# haasoscope_pro_power_board_-_5V.net
KiCad netlist of a schematic drawn in EAGLE
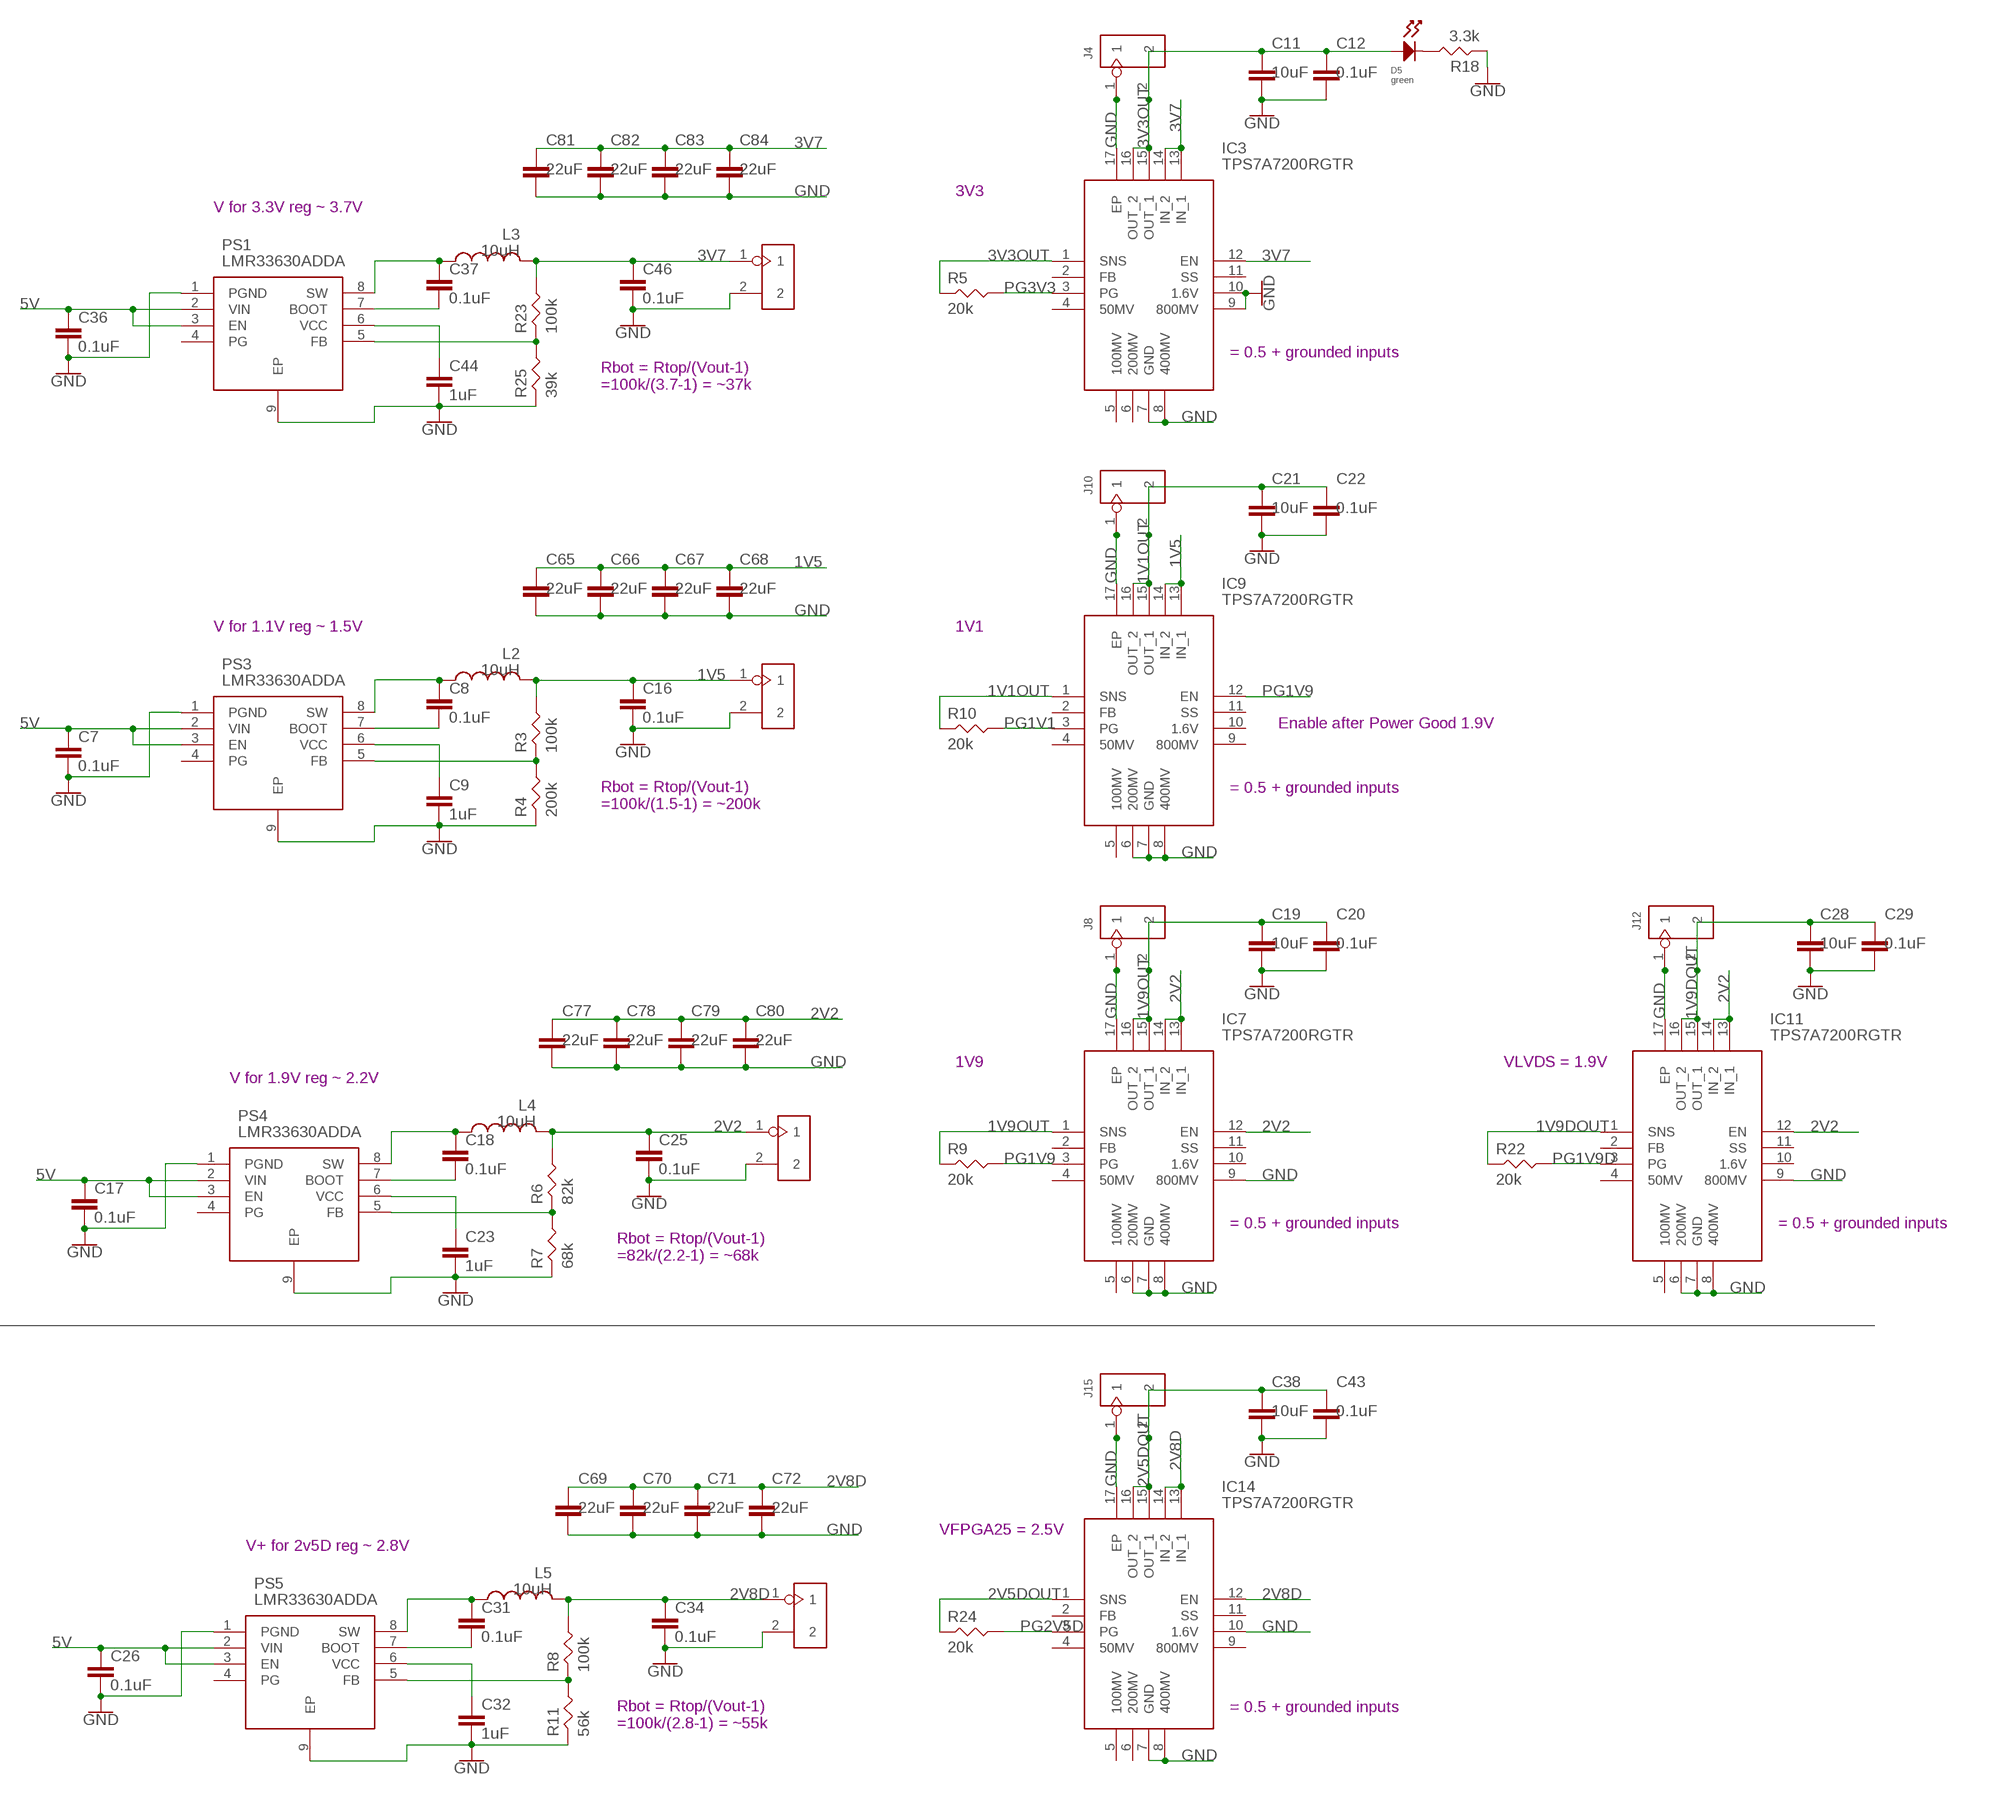
[diagram p0: schematic, sheet 1, part 1 of 2]
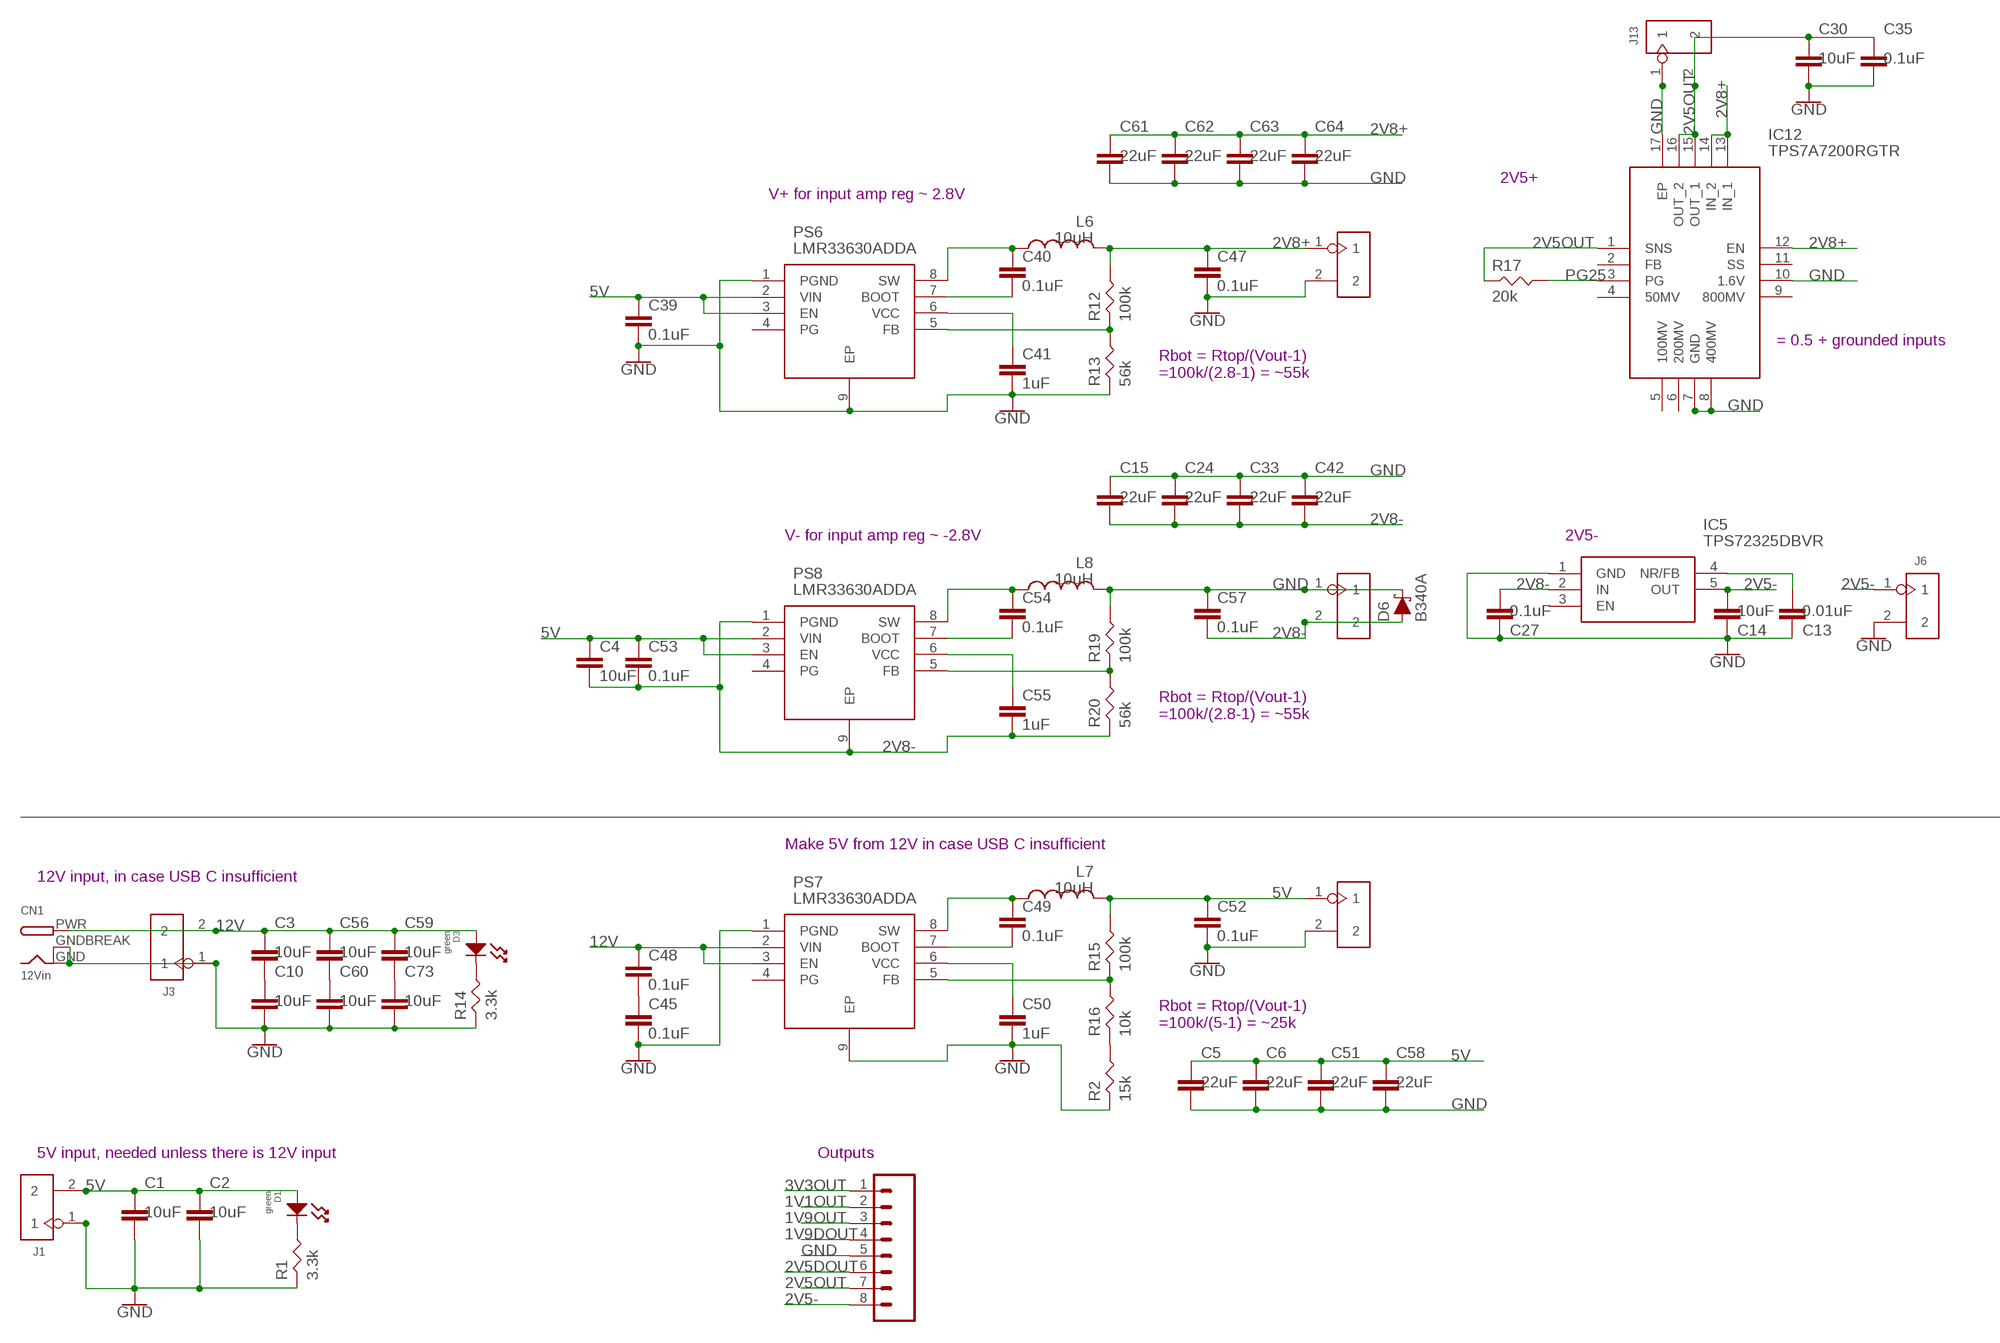
[diagram p1: schematic, sheet 1, part 2 of 2]

(export (version "E")
  (design (tool "Eeschema 10.0.6"))
  (components
    (comp (ref "C1")
      (value "10uF")
      (footprint "eagle-import:RESC0805_N")
      (libsource (lib "eagle-import") (part "CAPACITOR_0805_N"))
    )
    (comp (ref "C2")
      (value "10uF")
      (footprint "eagle-import:RESC0805_N")
      (libsource (lib "eagle-import") (part "CAPACITOR_0805_N"))
    )
    (comp (ref "C3")
      (value "10uF")
      (footprint "eagle-import:RESC0805_N")
      (libsource (lib "eagle-import") (part "CAPACITOR_0805_N"))
    )
    (comp (ref "C4")
      (value "10uF")
      (footprint "eagle-import:RESC0805_N")
      (libsource (lib "eagle-import") (part "CAPACITOR_0805_N"))
    )
    (comp (ref "C5")
      (value "22uF")
      (footprint "eagle-import:RESC0805_N")
      (libsource (lib "eagle-import") (part "CAPACITOR_0805_N"))
    )
    (comp (ref "C6")
      (value "22uF")
      (footprint "eagle-import:RESC0805_N")
      (libsource (lib "eagle-import") (part "CAPACITOR_0805_N"))
    )
    (comp (ref "C7")
      (value "0.1uF")
      (footprint "eagle-import:RESC0402_N")
      (libsource (lib "eagle-import") (part "CAPACITOR_0402_N"))
    )
    (comp (ref "C8")
      (value "0.1uF")
      (footprint "eagle-import:RESC0402_N")
      (libsource (lib "eagle-import") (part "CAPACITOR_0402_N"))
    )
    (comp (ref "C9")
      (value "1uF")
      (footprint "eagle-import:RESC0402_N")
      (libsource (lib "eagle-import") (part "CAPACITOR_0402_N"))
    )
    (comp (ref "C10")
      (value "10uF")
      (footprint "eagle-import:RESC0805_N")
      (libsource (lib "eagle-import") (part "CAPACITOR_0805_N"))
    )
    (comp (ref "C11")
      (value "10uF")
      (footprint "eagle-import:RESC0805_N")
      (libsource (lib "eagle-import") (part "CAPACITOR_0805_N"))
    )
    (comp (ref "C12")
      (value "0.1uF")
      (footprint "eagle-import:RESC0402_N")
      (libsource (lib "eagle-import") (part "CAPACITOR_0402_N"))
    )
    (comp (ref "C13")
      (value "0.01uF")
      (footprint "eagle-import:RESC0402_N")
      (libsource (lib "eagle-import") (part "CAPACITOR_0402_N"))
    )
    (comp (ref "C14")
      (value "10uF")
      (footprint "eagle-import:RESC0805_N")
      (libsource (lib "eagle-import") (part "CAPACITOR_0805_N"))
    )
    (comp (ref "C15")
      (value "22uF")
      (footprint "eagle-import:RESC0805_N")
      (libsource (lib "eagle-import") (part "CAPACITOR_0805_N"))
    )
    (comp (ref "C16")
      (value "0.1uF")
      (footprint "eagle-import:RESC0402_N")
      (libsource (lib "eagle-import") (part "CAPACITOR_0402_N"))
    )
    (comp (ref "C17")
      (value "0.1uF")
      (footprint "eagle-import:RESC0402_N")
      (libsource (lib "eagle-import") (part "CAPACITOR_0402_N"))
    )
    (comp (ref "C18")
      (value "0.1uF")
      (footprint "eagle-import:RESC0402_N")
      (libsource (lib "eagle-import") (part "CAPACITOR_0402_N"))
    )
    (comp (ref "C19")
      (value "10uF")
      (footprint "eagle-import:RESC0805_N")
      (libsource (lib "eagle-import") (part "CAPACITOR_0805_N"))
    )
    (comp (ref "C20")
      (value "0.1uF")
      (footprint "eagle-import:RESC0402_N")
      (libsource (lib "eagle-import") (part "CAPACITOR_0402_N"))
    )
    (comp (ref "C21")
      (value "10uF")
      (footprint "eagle-import:RESC0805_N")
      (libsource (lib "eagle-import") (part "CAPACITOR_0805_N"))
    )
    (comp (ref "C22")
      (value "0.1uF")
      (footprint "eagle-import:RESC0402_N")
      (libsource (lib "eagle-import") (part "CAPACITOR_0402_N"))
    )
    (comp (ref "C23")
      (value "1uF")
      (footprint "eagle-import:RESC0402_N")
      (libsource (lib "eagle-import") (part "CAPACITOR_0402_N"))
    )
    (comp (ref "C24")
      (value "22uF")
      (footprint "eagle-import:RESC0805_N")
      (libsource (lib "eagle-import") (part "CAPACITOR_0805_N"))
    )
    (comp (ref "C25")
      (value "0.1uF")
      (footprint "eagle-import:RESC0402_N")
      (libsource (lib "eagle-import") (part "CAPACITOR_0402_N"))
    )
    (comp (ref "C26")
      (value "0.1uF")
      (footprint "eagle-import:RESC0402_N")
      (libsource (lib "eagle-import") (part "CAPACITOR_0402_N"))
    )
    (comp (ref "C27")
      (value "0.1uF")
      (footprint "eagle-import:RESC0402_N")
      (libsource (lib "eagle-import") (part "CAPACITOR_0402_N"))
    )
    (comp (ref "C28")
      (value "10uF")
      (footprint "eagle-import:RESC0805_N")
      (libsource (lib "eagle-import") (part "CAPACITOR_0805_N"))
    )
    (comp (ref "C29")
      (value "0.1uF")
      (footprint "eagle-import:RESC0402_N")
      (libsource (lib "eagle-import") (part "CAPACITOR_0402_N"))
    )
    (comp (ref "C30")
      (value "10uF")
      (footprint "eagle-import:RESC0805_N")
      (libsource (lib "eagle-import") (part "CAPACITOR_0805_N"))
    )
    (comp (ref "C31")
      (value "0.1uF")
      (footprint "eagle-import:RESC0402_N")
      (libsource (lib "eagle-import") (part "CAPACITOR_0402_N"))
    )
    (comp (ref "C32")
      (value "1uF")
      (footprint "eagle-import:RESC0402_N")
      (libsource (lib "eagle-import") (part "CAPACITOR_0402_N"))
    )
    (comp (ref "C33")
      (value "22uF")
      (footprint "eagle-import:RESC0805_N")
      (libsource (lib "eagle-import") (part "CAPACITOR_0805_N"))
    )
    (comp (ref "C34")
      (value "0.1uF")
      (footprint "eagle-import:RESC0402_N")
      (libsource (lib "eagle-import") (part "CAPACITOR_0402_N"))
    )
    (comp (ref "C35")
      (value "0.1uF")
      (footprint "eagle-import:RESC0402_N")
      (libsource (lib "eagle-import") (part "CAPACITOR_0402_N"))
    )
    (comp (ref "C36")
      (value "0.1uF")
      (footprint "eagle-import:RESC0402_N")
      (libsource (lib "eagle-import") (part "CAPACITOR_0402_N"))
    )
    (comp (ref "C37")
      (value "0.1uF")
      (footprint "eagle-import:RESC0402_N")
      (libsource (lib "eagle-import") (part "CAPACITOR_0402_N"))
    )
    (comp (ref "C38")
      (value "10uF")
      (footprint "eagle-import:RESC0805_N")
      (libsource (lib "eagle-import") (part "CAPACITOR_0805_N"))
    )
    (comp (ref "C39")
      (value "0.1uF")
      (footprint "eagle-import:RESC0402_N")
      (libsource (lib "eagle-import") (part "CAPACITOR_0402_N"))
    )
    (comp (ref "C40")
      (value "0.1uF")
      (footprint "eagle-import:RESC0402_N")
      (libsource (lib "eagle-import") (part "CAPACITOR_0402_N"))
    )
    (comp (ref "C41")
      (value "1uF")
      (footprint "eagle-import:RESC0402_N")
      (libsource (lib "eagle-import") (part "CAPACITOR_0402_N"))
    )
    (comp (ref "C42")
      (value "22uF")
      (footprint "eagle-import:RESC0805_N")
      (libsource (lib "eagle-import") (part "CAPACITOR_0805_N"))
    )
    (comp (ref "C43")
      (value "0.1uF")
      (footprint "eagle-import:RESC0402_N")
      (libsource (lib "eagle-import") (part "CAPACITOR_0402_N"))
    )
    (comp (ref "C44")
      (value "1uF")
      (footprint "eagle-import:RESC0402_N")
      (libsource (lib "eagle-import") (part "CAPACITOR_0402_N"))
    )
    (comp (ref "C45")
      (value "0.1uF")
      (footprint "eagle-import:RESC0402_N")
      (libsource (lib "eagle-import") (part "CAPACITOR_0402_N"))
    )
    (comp (ref "C46")
      (value "0.1uF")
      (footprint "eagle-import:RESC0402_N")
      (libsource (lib "eagle-import") (part "CAPACITOR_0402_N"))
    )
    (comp (ref "C47")
      (value "0.1uF")
      (footprint "eagle-import:RESC0402_N")
      (libsource (lib "eagle-import") (part "CAPACITOR_0402_N"))
    )
    (comp (ref "C48")
      (value "0.1uF")
      (footprint "eagle-import:RESC0402_N")
      (libsource (lib "eagle-import") (part "CAPACITOR_0402_N"))
    )
    (comp (ref "C49")
      (value "0.1uF")
      (footprint "eagle-import:RESC0402_N")
      (libsource (lib "eagle-import") (part "CAPACITOR_0402_N"))
    )
    (comp (ref "C50")
      (value "1uF")
      (footprint "eagle-import:RESC0402_N")
      (libsource (lib "eagle-import") (part "CAPACITOR_0402_N"))
    )
    (comp (ref "C51")
      (value "22uF")
      (footprint "eagle-import:RESC0805_N")
      (libsource (lib "eagle-import") (part "CAPACITOR_0805_N"))
    )
    (comp (ref "C52")
      (value "0.1uF")
      (footprint "eagle-import:RESC0402_N")
      (libsource (lib "eagle-import") (part "CAPACITOR_0402_N"))
    )
    (comp (ref "C53")
      (value "0.1uF")
      (footprint "eagle-import:RESC0402_N")
      (libsource (lib "eagle-import") (part "CAPACITOR_0402_N"))
    )
    (comp (ref "C54")
      (value "0.1uF")
      (footprint "eagle-import:RESC0402_N")
      (libsource (lib "eagle-import") (part "CAPACITOR_0402_N"))
    )
    (comp (ref "C55")
      (value "1uF")
      (footprint "eagle-import:RESC0402_N")
      (libsource (lib "eagle-import") (part "CAPACITOR_0402_N"))
    )
    (comp (ref "C56")
      (value "10uF")
      (footprint "eagle-import:RESC0805_N")
      (libsource (lib "eagle-import") (part "CAPACITOR_0805_N"))
    )
    (comp (ref "C57")
      (value "0.1uF")
      (footprint "eagle-import:RESC0402_N")
      (libsource (lib "eagle-import") (part "CAPACITOR_0402_N"))
    )
    (comp (ref "C58")
      (value "22uF")
      (footprint "eagle-import:RESC0805_N")
      (libsource (lib "eagle-import") (part "CAPACITOR_0805_N"))
    )
    (comp (ref "C59")
      (value "10uF")
      (footprint "eagle-import:RESC0805_N")
      (libsource (lib "eagle-import") (part "CAPACITOR_0805_N"))
    )
    (comp (ref "C60")
      (value "10uF")
      (footprint "eagle-import:RESC0805_N")
      (libsource (lib "eagle-import") (part "CAPACITOR_0805_N"))
    )
    (comp (ref "C61")
      (value "22uF")
      (footprint "eagle-import:RESC0805_N")
      (libsource (lib "eagle-import") (part "CAPACITOR_0805_N"))
    )
    (comp (ref "C62")
      (value "22uF")
      (footprint "eagle-import:RESC0805_N")
      (libsource (lib "eagle-import") (part "CAPACITOR_0805_N"))
    )
    (comp (ref "C63")
      (value "22uF")
      (footprint "eagle-import:RESC0805_N")
      (libsource (lib "eagle-import") (part "CAPACITOR_0805_N"))
    )
    (comp (ref "C64")
      (value "22uF")
      (footprint "eagle-import:RESC0805_N")
      (libsource (lib "eagle-import") (part "CAPACITOR_0805_N"))
    )
    (comp (ref "C65")
      (value "22uF")
      (footprint "eagle-import:RESC0805_N")
      (libsource (lib "eagle-import") (part "CAPACITOR_0805_N"))
    )
    (comp (ref "C66")
      (value "22uF")
      (footprint "eagle-import:RESC0805_N")
      (libsource (lib "eagle-import") (part "CAPACITOR_0805_N"))
    )
    (comp (ref "C67")
      (value "22uF")
      (footprint "eagle-import:RESC0805_N")
      (libsource (lib "eagle-import") (part "CAPACITOR_0805_N"))
    )
    (comp (ref "C68")
      (value "22uF")
      (footprint "eagle-import:RESC0805_N")
      (libsource (lib "eagle-import") (part "CAPACITOR_0805_N"))
    )
    (comp (ref "C69")
      (value "22uF")
      (footprint "eagle-import:RESC0805_N")
      (libsource (lib "eagle-import") (part "CAPACITOR_0805_N"))
    )
    (comp (ref "C70")
      (value "22uF")
      (footprint "eagle-import:RESC0805_N")
      (libsource (lib "eagle-import") (part "CAPACITOR_0805_N"))
    )
    (comp (ref "C71")
      (value "22uF")
      (footprint "eagle-import:RESC0805_N")
      (libsource (lib "eagle-import") (part "CAPACITOR_0805_N"))
    )
    (comp (ref "C72")
      (value "22uF")
      (footprint "eagle-import:RESC0805_N")
      (libsource (lib "eagle-import") (part "CAPACITOR_0805_N"))
    )
    (comp (ref "C73")
      (value "10uF")
      (footprint "eagle-import:RESC0805_N")
      (libsource (lib "eagle-import") (part "CAPACITOR_0805_N"))
    )
    (comp (ref "C77")
      (value "22uF")
      (footprint "eagle-import:RESC0805_N")
      (libsource (lib "eagle-import") (part "CAPACITOR_0805_N"))
    )
    (comp (ref "C78")
      (value "22uF")
      (footprint "eagle-import:RESC0805_N")
      (libsource (lib "eagle-import") (part "CAPACITOR_0805_N"))
    )
    (comp (ref "C79")
      (value "22uF")
      (footprint "eagle-import:RESC0805_N")
      (libsource (lib "eagle-import") (part "CAPACITOR_0805_N"))
    )
    (comp (ref "C80")
      (value "22uF")
      (footprint "eagle-import:RESC0805_N")
      (libsource (lib "eagle-import") (part "CAPACITOR_0805_N"))
    )
    (comp (ref "C81")
      (value "22uF")
      (footprint "eagle-import:RESC0805_N")
      (libsource (lib "eagle-import") (part "CAPACITOR_0805_N"))
    )
    (comp (ref "C82")
      (value "22uF")
      (footprint "eagle-import:RESC0805_N")
      (libsource (lib "eagle-import") (part "CAPACITOR_0805_N"))
    )
    (comp (ref "C83")
      (value "22uF")
      (footprint "eagle-import:RESC0805_N")
      (libsource (lib "eagle-import") (part "CAPACITOR_0805_N"))
    )
    (comp (ref "C84")
      (value "22uF")
      (footprint "eagle-import:RESC0805_N")
      (libsource (lib "eagle-import") (part "CAPACITOR_0805_N"))
    )
    (comp (ref "CN1")
      (value "12Vin")
      (footprint "eagle-import:DCJACK_2MM_PTH")
      (libsource (lib "eagle-import") (part "DCBARRELPTH"))
    )
    (comp (ref "D1")
      (value "green")
      (footprint "eagle-import:LED0805")
      (fields (field (name "HOUSEPART") "NO"))
      (libsource (lib "eagle-import") (part "LED_SINGLE-0805"))
    )
    (comp (ref "D3")
      (value "green")
      (footprint "eagle-import:LED0805")
      (fields (field (name "HOUSEPART") "NO"))
      (libsource (lib "eagle-import") (part "LED_SINGLE-0805"))
    )
    (comp (ref "D5")
      (value "green")
      (footprint "eagle-import:LED0805")
      (fields (field (name "HOUSEPART") "NO"))
      (libsource (lib "eagle-import") (part "LED_SINGLE-0805"))
    )
    (comp (ref "D6")
      (value "B340A")
      (footprint "eagle-import:SMA-DIODE")
      (libsource (lib "eagle-import") (part "DIODE-SCHOTTKY-B340A"))
    )
    (comp (ref "IC3")
      (value "TPS7A7200RGTR")
      (footprint "eagle-import:QFN50P300X300X100-17N")
      (fields (field (name "MOUSER_PART_NUMBER") "595-TPS7A7200RGTR"))
      (libsource (lib "eagle-import") (part "TPS7A7200RGTR"))
    )
    (comp (ref "IC5")
      (value "TPS72325DBVR")
      (footprint "eagle-import:SOT95P280X145-5N")
      (fields (field (name "MOUSER_PART_NUMBER") "595-TPS72325DBVR"))
      (libsource (lib "eagle-import") (part "TPS72325DBVR"))
    )
    (comp (ref "IC7")
      (value "TPS7A7200RGTR")
      (footprint "eagle-import:QFN50P300X300X100-17N")
      (fields (field (name "MOUSER_PART_NUMBER") "595-TPS7A7200RGTR"))
      (libsource (lib "eagle-import") (part "TPS7A7200RGTR"))
    )
    (comp (ref "IC9")
      (value "TPS7A7200RGTR")
      (footprint "eagle-import:QFN50P300X300X100-17N")
      (fields (field (name "MOUSER_PART_NUMBER") "595-TPS7A7200RGTR"))
      (libsource (lib "eagle-import") (part "TPS7A7200RGTR"))
    )
    (comp (ref "IC11")
      (value "TPS7A7200RGTR")
      (footprint "eagle-import:QFN50P300X300X100-17N")
      (fields (field (name "MOUSER_PART_NUMBER") "595-TPS7A7200RGTR"))
      (libsource (lib "eagle-import") (part "TPS7A7200RGTR"))
    )
    (comp (ref "IC12")
      (value "TPS7A7200RGTR")
      (footprint "eagle-import:QFN50P300X300X100-17N")
      (fields (field (name "MOUSER_PART_NUMBER") "595-TPS7A7200RGTR"))
      (libsource (lib "eagle-import") (part "TPS7A7200RGTR"))
    )
    (comp (ref "IC14")
      (value "TPS7A7200RGTR")
      (footprint "eagle-import:QFN50P300X300X100-17N")
      (fields (field (name "MOUSER_PART_NUMBER") "595-TPS7A7200RGTR"))
      (libsource (lib "eagle-import") (part "TPS7A7200RGTR"))
    )
    (comp (ref "J1")
      (value "2p-2.54")
      (footprint "eagle-import:H2-2.54")
      (fields (field (name "MPN") "P125-1102A0BS116A1"))
      (libsource (lib "eagle-import") (part "DIP-BLACK-MALE-HEADER-VERT(2P-2.54)"))
    )
    (comp (ref "J2")
      (value "2p-2.54")
      (footprint "eagle-import:H2-2.54")
      (fields (field (name "MPN") "P125-1102A0BS116A1"))
      (libsource (lib "eagle-import") (part "DIP-BLACK-MALE-HEADER-VERT(2P-2.54)"))
    )
    (comp (ref "J3")
      (value "2p-2.54")
      (footprint "eagle-import:H2-2.54")
      (fields (field (name "MPN") "P125-1102A0BS116A1"))
      (libsource (lib "eagle-import") (part "DIP-BLACK-MALE-HEADER-VERT(2P-2.54)"))
    )
    (comp (ref "J4")
      (value "2p-2.54")
      (footprint "eagle-import:H2-2.54")
      (fields (field (name "MPN") "P125-1102A0BS116A1"))
      (libsource (lib "eagle-import") (part "DIP-BLACK-MALE-HEADER-VERT(2P-2.54)"))
    )
    (comp (ref "J5")
      (value "2p-2.54")
      (footprint "eagle-import:H2-2.54")
      (fields (field (name "MPN") "P125-1102A0BS116A1"))
      (libsource (lib "eagle-import") (part "DIP-BLACK-MALE-HEADER-VERT(2P-2.54)"))
    )
    (comp (ref "J6")
      (value "2p-2.54")
      (footprint "eagle-import:H2-2.54")
      (fields (field (name "MPN") "P125-1102A0BS116A1"))
      (libsource (lib "eagle-import") (part "DIP-BLACK-MALE-HEADER-VERT(2P-2.54)"))
    )
    (comp (ref "J7")
      (value "2p-2.54")
      (footprint "eagle-import:H2-2.54")
      (fields (field (name "MPN") "P125-1102A0BS116A1"))
      (libsource (lib "eagle-import") (part "DIP-BLACK-MALE-HEADER-VERT(2P-2.54)"))
    )
    (comp (ref "J8")
      (value "2p-2.54")
      (footprint "eagle-import:H2-2.54")
      (fields (field (name "MPN") "P125-1102A0BS116A1"))
      (libsource (lib "eagle-import") (part "DIP-BLACK-MALE-HEADER-VERT(2P-2.54)"))
    )
    (comp (ref "J9")
      (value "2p-2.54")
      (footprint "eagle-import:H2-2.54")
      (fields (field (name "MPN") "P125-1102A0BS116A1"))
      (libsource (lib "eagle-import") (part "DIP-BLACK-MALE-HEADER-VERT(2P-2.54)"))
    )
    (comp (ref "J10")
      (value "2p-2.54")
      (footprint "eagle-import:H2-2.54")
      (fields (field (name "MPN") "P125-1102A0BS116A1"))
      (libsource (lib "eagle-import") (part "DIP-BLACK-MALE-HEADER-VERT(2P-2.54)"))
    )
    (comp (ref "J11")
      (value "2p-2.54")
      (footprint "eagle-import:H2-2.54")
      (fields (field (name "MPN") "P125-1102A0BS116A1"))
      (libsource (lib "eagle-import") (part "DIP-BLACK-MALE-HEADER-VERT(2P-2.54)"))
    )
    (comp (ref "J12")
      (value "2p-2.54")
      (footprint "eagle-import:H2-2.54")
      (fields (field (name "MPN") "P125-1102A0BS116A1"))
      (libsource (lib "eagle-import") (part "DIP-BLACK-MALE-HEADER-VERT(2P-2.54)"))
    )
    (comp (ref "J13")
      (value "2p-2.54")
      (footprint "eagle-import:H2-2.54")
      (fields (field (name "MPN") "P125-1102A0BS116A1"))
      (libsource (lib "eagle-import") (part "DIP-BLACK-MALE-HEADER-VERT(2P-2.54)"))
    )
    (comp (ref "J14")
      (value "2p-2.54")
      (footprint "eagle-import:H2-2.54")
      (fields (field (name "MPN") "P125-1102A0BS116A1"))
      (libsource (lib "eagle-import") (part "DIP-BLACK-MALE-HEADER-VERT(2P-2.54)"))
    )
    (comp (ref "J15")
      (value "2p-2.54")
      (footprint "eagle-import:H2-2.54")
      (fields (field (name "MPN") "P125-1102A0BS116A1"))
      (libsource (lib "eagle-import") (part "DIP-BLACK-MALE-HEADER-VERT(2P-2.54)"))
    )
    (comp (ref "J16")
      (value "8pin")
      (footprint "eagle-import:1X08")
      (libsource (lib "eagle-import") (part "CONN_08{dblquote}"))
    )
    (comp (ref "J20")
      (value "2p-2.54")
      (footprint "eagle-import:H2-2.54")
      (fields (field (name "MPN") "P125-1102A0BS116A1"))
      (libsource (lib "eagle-import") (part "DIP-BLACK-MALE-HEADER-VERT(2P-2.54)"))
    )
    (comp (ref "L2")
      (value "10uH")
      (footprint "eagle-import:CDRH125")
      (libsource (lib "eagle-import") (part "INDUCTORPWR"))
    )
    (comp (ref "L3")
      (value "10uH")
      (footprint "eagle-import:CDRH125")
      (libsource (lib "eagle-import") (part "INDUCTORPWR"))
    )
    (comp (ref "L4")
      (value "10uH")
      (footprint "eagle-import:CDRH125")
      (libsource (lib "eagle-import") (part "INDUCTORPWR"))
    )
    (comp (ref "L5")
      (value "10uH")
      (footprint "eagle-import:CDRH125")
      (libsource (lib "eagle-import") (part "INDUCTORPWR"))
    )
    (comp (ref "L6")
      (value "10uH")
      (footprint "eagle-import:CDRH125")
      (libsource (lib "eagle-import") (part "INDUCTORPWR"))
    )
    (comp (ref "L7")
      (value "10uH")
      (footprint "eagle-import:CDRH125")
      (libsource (lib "eagle-import") (part "INDUCTORPWR"))
    )
    (comp (ref "L8")
      (value "10uH")
      (footprint "eagle-import:CDRH125")
      (libsource (lib "eagle-import") (part "INDUCTORPWR"))
    )
    (comp (ref "PS1")
      (value "LMR33630ADDA")
      (footprint "eagle-import:SOIC127P600X170-9N")
      (fields (field (name "MOUSER_PART_NUMBER") "595-LMR33630ADDA"))
      (libsource (lib "eagle-import") (part "LMR33630ADDA"))
    )
    (comp (ref "PS3")
      (value "LMR33630ADDA")
      (footprint "eagle-import:SOIC127P600X170-9N")
      (fields (field (name "MOUSER_PART_NUMBER") "595-LMR33630ADDA"))
      (libsource (lib "eagle-import") (part "LMR33630ADDA"))
    )
    (comp (ref "PS4")
      (value "LMR33630ADDA")
      (footprint "eagle-import:SOIC127P600X170-9N")
      (fields (field (name "MOUSER_PART_NUMBER") "595-LMR33630ADDA"))
      (libsource (lib "eagle-import") (part "LMR33630ADDA"))
    )
    (comp (ref "PS5")
      (value "LMR33630ADDA")
      (footprint "eagle-import:SOIC127P600X170-9N")
      (fields (field (name "MOUSER_PART_NUMBER") "595-LMR33630ADDA"))
      (libsource (lib "eagle-import") (part "LMR33630ADDA"))
    )
    (comp (ref "PS6")
      (value "LMR33630ADDA")
      (footprint "eagle-import:SOIC127P600X170-9N")
      (fields (field (name "MOUSER_PART_NUMBER") "595-LMR33630ADDA"))
      (libsource (lib "eagle-import") (part "LMR33630ADDA"))
    )
    (comp (ref "PS7")
      (value "LMR33630ADDA")
      (footprint "eagle-import:SOIC127P600X170-9N")
      (fields (field (name "MOUSER_PART_NUMBER") "595-LMR33630ADDA"))
      (libsource (lib "eagle-import") (part "LMR33630ADDA"))
    )
    (comp (ref "PS8")
      (value "LMR33630ADDA")
      (footprint "eagle-import:SOIC127P600X170-9N")
      (fields (field (name "MOUSER_PART_NUMBER") "595-LMR33630ADDA"))
      (libsource (lib "eagle-import") (part "LMR33630ADDA"))
    )
    (comp (ref "R1")
      (value "3.3k")
      (footprint "eagle-import:RES-0402")
      (libsource (lib "eagle-import") (part "RES-0402"))
    )
    (comp (ref "R2")
      (value "15k")
      (footprint "eagle-import:RES-0402")
      (libsource (lib "eagle-import") (part "RES-0402"))
    )
    (comp (ref "R3")
      (value "100k")
      (footprint "eagle-import:RES-0402")
      (libsource (lib "eagle-import") (part "RES-0402"))
    )
    (comp (ref "R4")
      (value "200k")
      (footprint "eagle-import:RES-0402")
      (libsource (lib "eagle-import") (part "RES-0402"))
    )
    (comp (ref "R5")
      (value "20k")
      (footprint "eagle-import:RES-0402")
      (libsource (lib "eagle-import") (part "RES-0402"))
    )
    (comp (ref "R6")
      (value "82k")
      (footprint "eagle-import:RES-0402")
      (libsource (lib "eagle-import") (part "RES-0402"))
    )
    (comp (ref "R7")
      (value "68k")
      (footprint "eagle-import:RES-0402")
      (libsource (lib "eagle-import") (part "RES-0402"))
    )
    (comp (ref "R8")
      (value "100k")
      (footprint "eagle-import:RES-0402")
      (libsource (lib "eagle-import") (part "RES-0402"))
    )
    (comp (ref "R9")
      (value "20k")
      (footprint "eagle-import:RES-0402")
      (libsource (lib "eagle-import") (part "RES-0402"))
    )
    (comp (ref "R10")
      (value "20k")
      (footprint "eagle-import:RES-0402")
      (libsource (lib "eagle-import") (part "RES-0402"))
    )
    (comp (ref "R11")
      (value "56k")
      (footprint "eagle-import:RES-0402")
      (libsource (lib "eagle-import") (part "RES-0402"))
    )
    (comp (ref "R12")
      (value "100k")
      (footprint "eagle-import:RES-0402")
      (libsource (lib "eagle-import") (part "RES-0402"))
    )
    (comp (ref "R13")
      (value "56k")
      (footprint "eagle-import:RES-0402")
      (libsource (lib "eagle-import") (part "RES-0402"))
    )
    (comp (ref "R14")
      (value "3.3k")
      (footprint "eagle-import:RES-0402")
      (libsource (lib "eagle-import") (part "RES-0402"))
    )
    (comp (ref "R15")
      (value "100k")
      (footprint "eagle-import:RES-0402")
      (libsource (lib "eagle-import") (part "RES-0402"))
    )
    (comp (ref "R16")
      (value "10k")
      (footprint "eagle-import:RES-0402")
      (libsource (lib "eagle-import") (part "RES-0402"))
    )
    (comp (ref "R17")
      (value "20k")
      (footprint "eagle-import:RES-0402")
      (libsource (lib "eagle-import") (part "RES-0402"))
    )
    (comp (ref "R18")
      (value "3.3k")
      (footprint "eagle-import:RES-0402")
      (libsource (lib "eagle-import") (part "RES-0402"))
    )
    (comp (ref "R19")
      (value "100k")
      (footprint "eagle-import:RES-0402")
      (libsource (lib "eagle-import") (part "RES-0402"))
    )
    (comp (ref "R20")
      (value "56k")
      (footprint "eagle-import:RES-0402")
      (libsource (lib "eagle-import") (part "RES-0402"))
    )
    (comp (ref "R22")
      (value "20k")
      (footprint "eagle-import:RES-0402")
      (libsource (lib "eagle-import") (part "RES-0402"))
    )
    (comp (ref "R23")
      (value "100k")
      (footprint "eagle-import:RES-0402")
      (libsource (lib "eagle-import") (part "RES-0402"))
    )
    (comp (ref "R24")
      (value "20k")
      (footprint "eagle-import:RES-0402")
      (libsource (lib "eagle-import") (part "RES-0402"))
    )
    (comp (ref "R25")
      (value "39k")
      (footprint "eagle-import:RES-0402")
      (libsource (lib "eagle-import") (part "RES-0402"))
    )
  )
  (nets
    (net (code "1") (name "/1V1OUT") (class "Default")
      (node (ref "C21") (pin "1") (pinfunction "1_1") (pintype "passive"))
      (node (ref "C22") (pin "1") (pinfunction "1_1") (pintype "passive"))
      (node (ref "IC9") (pin "1") (pinfunction "SNS_1") (pintype "bidirectional"))
      (node (ref "IC9") (pin "15") (pinfunction "OUT_1_15") (pintype "bidirectional"))
      (node (ref "IC9") (pin "16") (pinfunction "OUT_2_16") (pintype "bidirectional"))
      (node (ref "J10") (pin "2") (pinfunction "2_2") (pintype "bidirectional"))
      (node (ref "J16") (pin "2") (pinfunction "2_2") (pintype "passive"))
      (node (ref "R10") (pin "P$1") (pinfunction "P$1_P$1") (pintype "bidirectional"))
    )
    (net (code "2") (name "/1V5") (class "Default")
      (node (ref "C16") (pin "1") (pinfunction "1_1") (pintype "passive"))
      (node (ref "C65") (pin "1") (pinfunction "1_1") (pintype "passive"))
      (node (ref "C66") (pin "1") (pinfunction "1_1") (pintype "passive"))
      (node (ref "C67") (pin "1") (pinfunction "1_1") (pintype "passive"))
      (node (ref "C68") (pin "1") (pinfunction "1_1") (pintype "passive"))
      (node (ref "IC9") (pin "13") (pinfunction "IN_1_13") (pintype "bidirectional"))
      (node (ref "IC9") (pin "14") (pinfunction "IN_2_14") (pintype "bidirectional"))
      (node (ref "J2") (pin "1") (pinfunction "1_1") (pintype "bidirectional"))
      (node (ref "L2") (pin "2") (pinfunction "2_2") (pintype "passive"))
      (node (ref "R3") (pin "P$2") (pinfunction "P$2_P$2") (pintype "bidirectional"))
    )
    (net (code "3") (name "/1V9DOUT") (class "Default")
      (node (ref "C28") (pin "1") (pinfunction "1_1") (pintype "passive"))
      (node (ref "C29") (pin "1") (pinfunction "1_1") (pintype "passive"))
      (node (ref "IC11") (pin "1") (pinfunction "SNS_1") (pintype "bidirectional"))
      (node (ref "IC11") (pin "15") (pinfunction "OUT_1_15") (pintype "bidirectional"))
      (node (ref "IC11") (pin "16") (pinfunction "OUT_2_16") (pintype "bidirectional"))
      (node (ref "J12") (pin "2") (pinfunction "2_2") (pintype "bidirectional"))
      (node (ref "J16") (pin "4") (pinfunction "4_4") (pintype "passive"))
      (node (ref "R22") (pin "P$1") (pinfunction "P$1_P$1") (pintype "bidirectional"))
    )
    (net (code "4") (name "/1V9OUT") (class "Default")
      (node (ref "C19") (pin "1") (pinfunction "1_1") (pintype "passive"))
      (node (ref "C20") (pin "1") (pinfunction "1_1") (pintype "passive"))
      (node (ref "IC7") (pin "1") (pinfunction "SNS_1") (pintype "bidirectional"))
      (node (ref "IC7") (pin "15") (pinfunction "OUT_1_15") (pintype "bidirectional"))
      (node (ref "IC7") (pin "16") (pinfunction "OUT_2_16") (pintype "bidirectional"))
      (node (ref "J16") (pin "3") (pinfunction "3_3") (pintype "passive"))
      (node (ref "J8") (pin "2") (pinfunction "2_2") (pintype "bidirectional"))
      (node (ref "R9") (pin "P$1") (pinfunction "P$1_P$1") (pintype "bidirectional"))
    )
    (net (code "5") (name "/2V2") (class "Default")
      (node (ref "C25") (pin "1") (pinfunction "1_1") (pintype "passive"))
      (node (ref "C77") (pin "1") (pinfunction "1_1") (pintype "passive"))
      (node (ref "C78") (pin "1") (pinfunction "1_1") (pintype "passive"))
      (node (ref "C79") (pin "1") (pinfunction "1_1") (pintype "passive"))
      (node (ref "C80") (pin "1") (pinfunction "1_1") (pintype "passive"))
      (node (ref "IC11") (pin "12") (pinfunction "EN_12") (pintype "bidirectional"))
      (node (ref "IC11") (pin "13") (pinfunction "IN_1_13") (pintype "bidirectional"))
      (node (ref "IC11") (pin "14") (pinfunction "IN_2_14") (pintype "bidirectional"))
      (node (ref "IC7") (pin "12") (pinfunction "EN_12") (pintype "bidirectional"))
      (node (ref "IC7") (pin "13") (pinfunction "IN_1_13") (pintype "bidirectional"))
      (node (ref "IC7") (pin "14") (pinfunction "IN_2_14") (pintype "bidirectional"))
      (node (ref "J5") (pin "1") (pinfunction "1_1") (pintype "bidirectional"))
      (node (ref "L4") (pin "2") (pinfunction "2_2") (pintype "passive"))
      (node (ref "R6") (pin "P$2") (pinfunction "P$2_P$2") (pintype "bidirectional"))
    )
    (net (code "6") (name "/2V5-") (class "Default")
      (node (ref "C14") (pin "1") (pinfunction "1_1") (pintype "passive"))
      (node (ref "IC5") (pin "5") (pinfunction "OUT_5") (pintype "bidirectional"))
      (node (ref "J16") (pin "8") (pinfunction "8_8") (pintype "passive"))
      (node (ref "J6") (pin "1") (pinfunction "1_1") (pintype "bidirectional"))
    )
    (net (code "7") (name "/2V5DOUT") (class "Default")
      (node (ref "C38") (pin "1") (pinfunction "1_1") (pintype "passive"))
      (node (ref "C43") (pin "1") (pinfunction "1_1") (pintype "passive"))
      (node (ref "IC14") (pin "1") (pinfunction "SNS_1") (pintype "bidirectional"))
      (node (ref "IC14") (pin "15") (pinfunction "OUT_1_15") (pintype "bidirectional"))
      (node (ref "IC14") (pin "16") (pinfunction "OUT_2_16") (pintype "bidirectional"))
      (node (ref "J15") (pin "2") (pinfunction "2_2") (pintype "bidirectional"))
      (node (ref "J16") (pin "6") (pinfunction "6_6") (pintype "passive"))
      (node (ref "R24") (pin "P$1") (pinfunction "P$1_P$1") (pintype "bidirectional"))
    )
    (net (code "8") (name "/2V5OUT") (class "Default")
      (node (ref "C30") (pin "1") (pinfunction "1_1") (pintype "passive"))
      (node (ref "C35") (pin "1") (pinfunction "1_1") (pintype "passive"))
      (node (ref "IC12") (pin "1") (pinfunction "SNS_1") (pintype "bidirectional"))
      (node (ref "IC12") (pin "15") (pinfunction "OUT_1_15") (pintype "bidirectional"))
      (node (ref "IC12") (pin "16") (pinfunction "OUT_2_16") (pintype "bidirectional"))
      (node (ref "J13") (pin "2") (pinfunction "2_2") (pintype "bidirectional"))
      (node (ref "J16") (pin "7") (pinfunction "7_7") (pintype "passive"))
      (node (ref "R17") (pin "P$1") (pinfunction "P$1_P$1") (pintype "bidirectional"))
    )
    (net (code "9") (name "/2V8+") (class "Default")
      (node (ref "C47") (pin "1") (pinfunction "1_1") (pintype "passive"))
      (node (ref "C61") (pin "1") (pinfunction "1_1") (pintype "passive"))
      (node (ref "C62") (pin "1") (pinfunction "1_1") (pintype "passive"))
      (node (ref "C63") (pin "1") (pinfunction "1_1") (pintype "passive"))
      (node (ref "C64") (pin "1") (pinfunction "1_1") (pintype "passive"))
      (node (ref "IC12") (pin "12") (pinfunction "EN_12") (pintype "bidirectional"))
      (node (ref "IC12") (pin "13") (pinfunction "IN_1_13") (pintype "bidirectional"))
      (node (ref "IC12") (pin "14") (pinfunction "IN_2_14") (pintype "bidirectional"))
      (node (ref "J9") (pin "1") (pinfunction "1_1") (pintype "bidirectional"))
      (node (ref "L6") (pin "2") (pinfunction "2_2") (pintype "passive"))
      (node (ref "R12") (pin "P$2") (pinfunction "P$2_P$2") (pintype "bidirectional"))
    )
    (net (code "10") (name "/2V8-") (class "Default")
      (node (ref "C15") (pin "2") (pinfunction "2_2") (pintype "passive"))
      (node (ref "C24") (pin "2") (pinfunction "2_2") (pintype "passive"))
      (node (ref "C27") (pin "1") (pinfunction "1_1") (pintype "passive"))
      (node (ref "C33") (pin "2") (pinfunction "2_2") (pintype "passive"))
      (node (ref "C4") (pin "2") (pinfunction "2_2") (pintype "passive"))
      (node (ref "C42") (pin "2") (pinfunction "2_2") (pintype "passive"))
      (node (ref "C53") (pin "2") (pinfunction "2_2") (pintype "passive"))
      (node (ref "C55") (pin "2") (pinfunction "2_2") (pintype "passive"))
      (node (ref "C57") (pin "2") (pinfunction "2_2") (pintype "passive"))
      (node (ref "D6") (pin "A") (pinfunction "A_A") (pintype "passive"))
      (node (ref "IC5") (pin "2") (pinfunction "IN_2") (pintype "bidirectional"))
      (node (ref "J20") (pin "2") (pinfunction "2_2") (pintype "bidirectional"))
      (node (ref "PS8") (pin "1") (pinfunction "PGND_1") (pintype "bidirectional"))
      (node (ref "PS8") (pin "9") (pinfunction "EP_9") (pintype "bidirectional"))
      (node (ref "R20") (pin "P$1") (pinfunction "P$1_P$1") (pintype "bidirectional"))
    )
    (net (code "11") (name "/2V8D") (class "Default")
      (node (ref "C34") (pin "1") (pinfunction "1_1") (pintype "passive"))
      (node (ref "C69") (pin "1") (pinfunction "1_1") (pintype "passive"))
      (node (ref "C70") (pin "1") (pinfunction "1_1") (pintype "passive"))
      (node (ref "C71") (pin "1") (pinfunction "1_1") (pintype "passive"))
      (node (ref "C72") (pin "1") (pinfunction "1_1") (pintype "passive"))
      (node (ref "IC14") (pin "12") (pinfunction "EN_12") (pintype "bidirectional"))
      (node (ref "IC14") (pin "13") (pinfunction "IN_1_13") (pintype "bidirectional"))
      (node (ref "IC14") (pin "14") (pinfunction "IN_2_14") (pintype "bidirectional"))
      (node (ref "J7") (pin "1") (pinfunction "1_1") (pintype "bidirectional"))
      (node (ref "L5") (pin "2") (pinfunction "2_2") (pintype "passive"))
      (node (ref "R8") (pin "P$2") (pinfunction "P$2_P$2") (pintype "bidirectional"))
    )
    (net (code "12") (name "/3V3OUT") (class "Default")
      (node (ref "C11") (pin "1") (pinfunction "1_1") (pintype "passive"))
      (node (ref "C12") (pin "1") (pinfunction "1_1") (pintype "passive"))
      (node (ref "D5") (pin "ANODE") (pinfunction "ANODE_ANODE") (pintype "power_in"))
      (node (ref "IC3") (pin "1") (pinfunction "SNS_1") (pintype "bidirectional"))
      (node (ref "IC3") (pin "15") (pinfunction "OUT_1_15") (pintype "bidirectional"))
      (node (ref "IC3") (pin "16") (pinfunction "OUT_2_16") (pintype "bidirectional"))
      (node (ref "J16") (pin "1") (pinfunction "1_1") (pintype "passive"))
      (node (ref "J4") (pin "2") (pinfunction "2_2") (pintype "bidirectional"))
      (node (ref "R5") (pin "P$1") (pinfunction "P$1_P$1") (pintype "bidirectional"))
    )
    (net (code "13") (name "/3V7") (class "Default")
      (node (ref "C46") (pin "1") (pinfunction "1_1") (pintype "passive"))
      (node (ref "C81") (pin "1") (pinfunction "1_1") (pintype "passive"))
      (node (ref "C82") (pin "1") (pinfunction "1_1") (pintype "passive"))
      (node (ref "C83") (pin "1") (pinfunction "1_1") (pintype "passive"))
      (node (ref "C84") (pin "1") (pinfunction "1_1") (pintype "passive"))
      (node (ref "IC3") (pin "12") (pinfunction "EN_12") (pintype "bidirectional"))
      (node (ref "IC3") (pin "13") (pinfunction "IN_1_13") (pintype "bidirectional"))
      (node (ref "IC3") (pin "14") (pinfunction "IN_2_14") (pintype "bidirectional"))
      (node (ref "J14") (pin "1") (pinfunction "1_1") (pintype "bidirectional"))
      (node (ref "L3") (pin "2") (pinfunction "2_2") (pintype "passive"))
      (node (ref "R23") (pin "P$2") (pinfunction "P$2_P$2") (pintype "bidirectional"))
    )
    (net (code "14") (name "/5V") (class "Default")
      (node (ref "C1") (pin "1") (pinfunction "1_1") (pintype "passive"))
      (node (ref "C17") (pin "1") (pinfunction "1_1") (pintype "passive"))
      (node (ref "C2") (pin "1") (pinfunction "1_1") (pintype "passive"))
      (node (ref "C26") (pin "1") (pinfunction "1_1") (pintype "passive"))
      (node (ref "C36") (pin "1") (pinfunction "1_1") (pintype "passive"))
      (node (ref "C39") (pin "1") (pinfunction "1_1") (pintype "passive"))
      (node (ref "C4") (pin "1") (pinfunction "1_1") (pintype "passive"))
      (node (ref "C5") (pin "1") (pinfunction "1_1") (pintype "passive"))
      (node (ref "C51") (pin "1") (pinfunction "1_1") (pintype "passive"))
      (node (ref "C52") (pin "1") (pinfunction "1_1") (pintype "passive"))
      (node (ref "C53") (pin "1") (pinfunction "1_1") (pintype "passive"))
      (node (ref "C58") (pin "1") (pinfunction "1_1") (pintype "passive"))
      (node (ref "C6") (pin "1") (pinfunction "1_1") (pintype "passive"))
      (node (ref "C7") (pin "1") (pinfunction "1_1") (pintype "passive"))
      (node (ref "D1") (pin "ANODE") (pinfunction "ANODE_ANODE") (pintype "power_in"))
      (node (ref "J1") (pin "2") (pinfunction "2_2") (pintype "bidirectional"))
      (node (ref "J11") (pin "1") (pinfunction "1_1") (pintype "bidirectional"))
      (node (ref "L7") (pin "2") (pinfunction "2_2") (pintype "passive"))
      (node (ref "PS1") (pin "2") (pinfunction "VIN_2") (pintype "bidirectional"))
      (node (ref "PS1") (pin "3") (pinfunction "EN_3") (pintype "bidirectional"))
      (node (ref "PS3") (pin "2") (pinfunction "VIN_2") (pintype "bidirectional"))
      (node (ref "PS3") (pin "3") (pinfunction "EN_3") (pintype "bidirectional"))
      (node (ref "PS4") (pin "2") (pinfunction "VIN_2") (pintype "bidirectional"))
      (node (ref "PS4") (pin "3") (pinfunction "EN_3") (pintype "bidirectional"))
      (node (ref "PS5") (pin "2") (pinfunction "VIN_2") (pintype "bidirectional"))
      (node (ref "PS5") (pin "3") (pinfunction "EN_3") (pintype "bidirectional"))
      (node (ref "PS6") (pin "2") (pinfunction "VIN_2") (pintype "bidirectional"))
      (node (ref "PS6") (pin "3") (pinfunction "EN_3") (pintype "bidirectional"))
      (node (ref "PS8") (pin "2") (pinfunction "VIN_2") (pintype "bidirectional"))
      (node (ref "PS8") (pin "3") (pinfunction "EN_3") (pintype "bidirectional"))
      (node (ref "R15") (pin "P$2") (pinfunction "P$2_P$2") (pintype "bidirectional"))
    )
    (net (code "15") (name "/12V") (class "Default")
      (node (ref "C3") (pin "1") (pinfunction "1_1") (pintype "passive"))
      (node (ref "C48") (pin "1") (pinfunction "1_1") (pintype "passive"))
      (node (ref "C56") (pin "1") (pinfunction "1_1") (pintype "passive"))
      (node (ref "C59") (pin "1") (pinfunction "1_1") (pintype "passive"))
      (node (ref "CN1") (pin "PWR") (pinfunction "PWR_PWR") (pintype "power_in"))
      (node (ref "D3") (pin "ANODE") (pinfunction "ANODE_ANODE") (pintype "power_in"))
      (node (ref "J3") (pin "2") (pinfunction "2_2") (pintype "bidirectional"))
      (node (ref "PS7") (pin "2") (pinfunction "VIN_2") (pintype "bidirectional"))
      (node (ref "PS7") (pin "3") (pinfunction "EN_3") (pintype "bidirectional"))
    )
    (net (code "16") (name "/PG1V1") (class "Default")
      (node (ref "IC9") (pin "3") (pinfunction "PG_3") (pintype "bidirectional"))
      (node (ref "R10") (pin "P$2") (pinfunction "P$2_P$2") (pintype "bidirectional"))
    )
    (net (code "17") (name "/PG1V9") (class "Default")
      (node (ref "IC7") (pin "3") (pinfunction "PG_3") (pintype "bidirectional"))
      (node (ref "IC9") (pin "12") (pinfunction "EN_12") (pintype "bidirectional"))
      (node (ref "R9") (pin "P$2") (pinfunction "P$2_P$2") (pintype "bidirectional"))
    )
    (net (code "18") (name "/PG1V9D") (class "Default")
      (node (ref "IC11") (pin "3") (pinfunction "PG_3") (pintype "bidirectional"))
      (node (ref "R22") (pin "P$2") (pinfunction "P$2_P$2") (pintype "bidirectional"))
    )
    (net (code "19") (name "/PG2V5D") (class "Default")
      (node (ref "IC14") (pin "3") (pinfunction "PG_3") (pintype "bidirectional"))
      (node (ref "R24") (pin "P$2") (pinfunction "P$2_P$2") (pintype "bidirectional"))
    )
    (net (code "20") (name "/PG3V3") (class "Default")
      (node (ref "IC3") (pin "3") (pinfunction "PG_3") (pintype "bidirectional"))
      (node (ref "R5") (pin "P$2") (pinfunction "P$2_P$2") (pintype "bidirectional"))
    )
    (net (code "21") (name "/PG25") (class "Default")
      (node (ref "IC12") (pin "3") (pinfunction "PG_3") (pintype "bidirectional"))
      (node (ref "R17") (pin "P$2") (pinfunction "P$2_P$2") (pintype "bidirectional"))
    )
    (net (code "22") (name "GND") (class "Default")
      (node (ref "C1") (pin "2") (pinfunction "2_2") (pintype "passive"))
      (node (ref "C10") (pin "2") (pinfunction "2_2") (pintype "passive"))
      (node (ref "C11") (pin "2") (pinfunction "2_2") (pintype "passive"))
      (node (ref "C12") (pin "2") (pinfunction "2_2") (pintype "passive"))
      (node (ref "C13") (pin "2") (pinfunction "2_2") (pintype "passive"))
      (node (ref "C14") (pin "2") (pinfunction "2_2") (pintype "passive"))
      (node (ref "C15") (pin "1") (pinfunction "1_1") (pintype "passive"))
      (node (ref "C16") (pin "2") (pinfunction "2_2") (pintype "passive"))
      (node (ref "C17") (pin "2") (pinfunction "2_2") (pintype "passive"))
      (node (ref "C19") (pin "2") (pinfunction "2_2") (pintype "passive"))
      (node (ref "C2") (pin "2") (pinfunction "2_2") (pintype "passive"))
      (node (ref "C20") (pin "2") (pinfunction "2_2") (pintype "passive"))
      (node (ref "C21") (pin "2") (pinfunction "2_2") (pintype "passive"))
      (node (ref "C22") (pin "2") (pinfunction "2_2") (pintype "passive"))
      (node (ref "C23") (pin "2") (pinfunction "2_2") (pintype "passive"))
      (node (ref "C24") (pin "1") (pinfunction "1_1") (pintype "passive"))
      (node (ref "C25") (pin "2") (pinfunction "2_2") (pintype "passive"))
      (node (ref "C26") (pin "2") (pinfunction "2_2") (pintype "passive"))
      (node (ref "C27") (pin "2") (pinfunction "2_2") (pintype "passive"))
      (node (ref "C28") (pin "2") (pinfunction "2_2") (pintype "passive"))
      (node (ref "C29") (pin "2") (pinfunction "2_2") (pintype "passive"))
      (node (ref "C30") (pin "2") (pinfunction "2_2") (pintype "passive"))
      (node (ref "C32") (pin "2") (pinfunction "2_2") (pintype "passive"))
      (node (ref "C33") (pin "1") (pinfunction "1_1") (pintype "passive"))
      (node (ref "C34") (pin "2") (pinfunction "2_2") (pintype "passive"))
      (node (ref "C35") (pin "2") (pinfunction "2_2") (pintype "passive"))
      (node (ref "C36") (pin "2") (pinfunction "2_2") (pintype "passive"))
      (node (ref "C38") (pin "2") (pinfunction "2_2") (pintype "passive"))
      (node (ref "C39") (pin "2") (pinfunction "2_2") (pintype "passive"))
      (node (ref "C41") (pin "2") (pinfunction "2_2") (pintype "passive"))
      (node (ref "C42") (pin "1") (pinfunction "1_1") (pintype "passive"))
      (node (ref "C43") (pin "2") (pinfunction "2_2") (pintype "passive"))
      (node (ref "C44") (pin "2") (pinfunction "2_2") (pintype "passive"))
      (node (ref "C45") (pin "2") (pinfunction "2_2") (pintype "passive"))
      (node (ref "C46") (pin "2") (pinfunction "2_2") (pintype "passive"))
      (node (ref "C47") (pin "2") (pinfunction "2_2") (pintype "passive"))
      (node (ref "C5") (pin "2") (pinfunction "2_2") (pintype "passive"))
      (node (ref "C50") (pin "2") (pinfunction "2_2") (pintype "passive"))
      (node (ref "C51") (pin "2") (pinfunction "2_2") (pintype "passive"))
      (node (ref "C52") (pin "2") (pinfunction "2_2") (pintype "passive"))
      (node (ref "C57") (pin "1") (pinfunction "1_1") (pintype "passive"))
      (node (ref "C58") (pin "2") (pinfunction "2_2") (pintype "passive"))
      (node (ref "C6") (pin "2") (pinfunction "2_2") (pintype "passive"))
      (node (ref "C60") (pin "2") (pinfunction "2_2") (pintype "passive"))
      (node (ref "C61") (pin "2") (pinfunction "2_2") (pintype "passive"))
      (node (ref "C62") (pin "2") (pinfunction "2_2") (pintype "passive"))
      (node (ref "C63") (pin "2") (pinfunction "2_2") (pintype "passive"))
      (node (ref "C64") (pin "2") (pinfunction "2_2") (pintype "passive"))
      (node (ref "C65") (pin "2") (pinfunction "2_2") (pintype "passive"))
      (node (ref "C66") (pin "2") (pinfunction "2_2") (pintype "passive"))
      (node (ref "C67") (pin "2") (pinfunction "2_2") (pintype "passive"))
      (node (ref "C68") (pin "2") (pinfunction "2_2") (pintype "passive"))
      (node (ref "C69") (pin "2") (pinfunction "2_2") (pintype "passive"))
      (node (ref "C7") (pin "2") (pinfunction "2_2") (pintype "passive"))
      (node (ref "C70") (pin "2") (pinfunction "2_2") (pintype "passive"))
      (node (ref "C71") (pin "2") (pinfunction "2_2") (pintype "passive"))
      (node (ref "C72") (pin "2") (pinfunction "2_2") (pintype "passive"))
      (node (ref "C73") (pin "2") (pinfunction "2_2") (pintype "passive"))
      (node (ref "C77") (pin "2") (pinfunction "2_2") (pintype "passive"))
      (node (ref "C78") (pin "2") (pinfunction "2_2") (pintype "passive"))
      (node (ref "C79") (pin "2") (pinfunction "2_2") (pintype "passive"))
      (node (ref "C80") (pin "2") (pinfunction "2_2") (pintype "passive"))
      (node (ref "C81") (pin "2") (pinfunction "2_2") (pintype "passive"))
      (node (ref "C82") (pin "2") (pinfunction "2_2") (pintype "passive"))
      (node (ref "C83") (pin "2") (pinfunction "2_2") (pintype "passive"))
      (node (ref "C84") (pin "2") (pinfunction "2_2") (pintype "passive"))
      (node (ref "C9") (pin "2") (pinfunction "2_2") (pintype "passive"))
      (node (ref "CN1") (pin "GND") (pinfunction "GND_GND") (pintype "power_in"))
      (node (ref "CN1") (pin "GNDBREAK") (pinfunction "GNDBREAK_GNDBREAK") (pintype "power_in"))
      (node (ref "D6") (pin "C") (pinfunction "C_C") (pintype "passive"))
      (node (ref "IC11") (pin "17") (pinfunction "EP_17") (pintype "bidirectional"))
      (node (ref "IC11") (pin "6") (pinfunction "200MV_6") (pintype "bidirectional"))
      (node (ref "IC11") (pin "7") (pinfunction "GND_7") (pintype "bidirectional"))
      (node (ref "IC11") (pin "8") (pinfunction "400MV_8") (pintype "bidirectional"))
      (node (ref "IC11") (pin "9") (pinfunction "800MV_9") (pintype "bidirectional"))
      (node (ref "IC12") (pin "10") (pinfunction "1.6V_10") (pintype "bidirectional"))
      (node (ref "IC12") (pin "17") (pinfunction "EP_17") (pintype "bidirectional"))
      (node (ref "IC12") (pin "7") (pinfunction "GND_7") (pintype "bidirectional"))
      (node (ref "IC12") (pin "8") (pinfunction "400MV_8") (pintype "bidirectional"))
      (node (ref "IC14") (pin "10") (pinfunction "1.6V_10") (pintype "bidirectional"))
      (node (ref "IC14") (pin "17") (pinfunction "EP_17") (pintype "bidirectional"))
      (node (ref "IC14") (pin "7") (pinfunction "GND_7") (pintype "bidirectional"))
      (node (ref "IC14") (pin "8") (pinfunction "400MV_8") (pintype "bidirectional"))
      (node (ref "IC3") (pin "10") (pinfunction "1.6V_10") (pintype "bidirectional"))
      (node (ref "IC3") (pin "17") (pinfunction "EP_17") (pintype "bidirectional"))
      (node (ref "IC3") (pin "7") (pinfunction "GND_7") (pintype "bidirectional"))
      (node (ref "IC3") (pin "8") (pinfunction "400MV_8") (pintype "bidirectional"))
      (node (ref "IC3") (pin "9") (pinfunction "800MV_9") (pintype "bidirectional"))
      (node (ref "IC5") (pin "1") (pinfunction "GND_1") (pintype "bidirectional"))
      (node (ref "IC7") (pin "17") (pinfunction "EP_17") (pintype "bidirectional"))
      (node (ref "IC7") (pin "6") (pinfunction "200MV_6") (pintype "bidirectional"))
      (node (ref "IC7") (pin "7") (pinfunction "GND_7") (pintype "bidirectional"))
      (node (ref "IC7") (pin "8") (pinfunction "400MV_8") (pintype "bidirectional"))
      (node (ref "IC7") (pin "9") (pinfunction "800MV_9") (pintype "bidirectional"))
      (node (ref "IC9") (pin "17") (pinfunction "EP_17") (pintype "bidirectional"))
      (node (ref "IC9") (pin "6") (pinfunction "200MV_6") (pintype "bidirectional"))
      (node (ref "IC9") (pin "7") (pinfunction "GND_7") (pintype "bidirectional"))
      (node (ref "IC9") (pin "8") (pinfunction "400MV_8") (pintype "bidirectional"))
      (node (ref "J1") (pin "1") (pinfunction "1_1") (pintype "bidirectional"))
      (node (ref "J10") (pin "1") (pinfunction "1_1") (pintype "bidirectional"))
      (node (ref "J11") (pin "2") (pinfunction "2_2") (pintype "bidirectional"))
      (node (ref "J12") (pin "1") (pinfunction "1_1") (pintype "bidirectional"))
      (node (ref "J13") (pin "1") (pinfunction "1_1") (pintype "bidirectional"))
      (node (ref "J14") (pin "2") (pinfunction "2_2") (pintype "bidirectional"))
      (node (ref "J15") (pin "1") (pinfunction "1_1") (pintype "bidirectional"))
      (node (ref "J16") (pin "5") (pinfunction "5_5") (pintype "passive"))
      (node (ref "J2") (pin "2") (pinfunction "2_2") (pintype "bidirectional"))
      (node (ref "J20") (pin "1") (pinfunction "1_1") (pintype "bidirectional"))
      (node (ref "J3") (pin "1") (pinfunction "1_1") (pintype "bidirectional"))
      (node (ref "J4") (pin "1") (pinfunction "1_1") (pintype "bidirectional"))
      (node (ref "J5") (pin "2") (pinfunction "2_2") (pintype "bidirectional"))
      (node (ref "J6") (pin "2") (pinfunction "2_2") (pintype "bidirectional"))
      (node (ref "J7") (pin "2") (pinfunction "2_2") (pintype "bidirectional"))
      (node (ref "J8") (pin "1") (pinfunction "1_1") (pintype "bidirectional"))
      (node (ref "J9") (pin "2") (pinfunction "2_2") (pintype "bidirectional"))
      (node (ref "L8") (pin "2") (pinfunction "2_2") (pintype "passive"))
      (node (ref "PS1") (pin "1") (pinfunction "PGND_1") (pintype "bidirectional"))
      (node (ref "PS1") (pin "9") (pinfunction "EP_9") (pintype "bidirectional"))
      (node (ref "PS3") (pin "1") (pinfunction "PGND_1") (pintype "bidirectional"))
      (node (ref "PS3") (pin "9") (pinfunction "EP_9") (pintype "bidirectional"))
      (node (ref "PS4") (pin "1") (pinfunction "PGND_1") (pintype "bidirectional"))
      (node (ref "PS4") (pin "9") (pinfunction "EP_9") (pintype "bidirectional"))
      (node (ref "PS5") (pin "1") (pinfunction "PGND_1") (pintype "bidirectional"))
      (node (ref "PS5") (pin "9") (pinfunction "EP_9") (pintype "bidirectional"))
      (node (ref "PS6") (pin "1") (pinfunction "PGND_1") (pintype "bidirectional"))
      (node (ref "PS6") (pin "9") (pinfunction "EP_9") (pintype "bidirectional"))
      (node (ref "PS7") (pin "1") (pinfunction "PGND_1") (pintype "bidirectional"))
      (node (ref "PS7") (pin "9") (pinfunction "EP_9") (pintype "bidirectional"))
      (node (ref "R1") (pin "P$1") (pinfunction "P$1_P$1") (pintype "bidirectional"))
      (node (ref "R11") (pin "P$1") (pinfunction "P$1_P$1") (pintype "bidirectional"))
      (node (ref "R13") (pin "P$1") (pinfunction "P$1_P$1") (pintype "bidirectional"))
      (node (ref "R14") (pin "P$1") (pinfunction "P$1_P$1") (pintype "bidirectional"))
      (node (ref "R18") (pin "P$1") (pinfunction "P$1_P$1") (pintype "bidirectional"))
      (node (ref "R19") (pin "P$2") (pinfunction "P$2_P$2") (pintype "bidirectional"))
      (node (ref "R2") (pin "P$1") (pinfunction "P$1_P$1") (pintype "bidirectional"))
      (node (ref "R25") (pin "P$1") (pinfunction "P$1_P$1") (pintype "bidirectional"))
      (node (ref "R4") (pin "P$1") (pinfunction "P$1_P$1") (pintype "bidirectional"))
      (node (ref "R7") (pin "P$1") (pinfunction "P$1_P$1") (pintype "bidirectional"))
    )
    (net (code "23") (name "Net-(C10-Pad1)") (class "Default")
      (node (ref "C10") (pin "1") (pinfunction "1_1") (pintype "passive"))
      (node (ref "C3") (pin "2") (pinfunction "2_2") (pintype "passive"))
    )
    (net (code "24") (name "Net-(C45-Pad1)") (class "Default")
      (node (ref "C45") (pin "1") (pinfunction "1_1") (pintype "passive"))
      (node (ref "C48") (pin "2") (pinfunction "2_2") (pintype "passive"))
    )
    (net (code "25") (name "Net-(C56-Pad2)") (class "Default")
      (node (ref "C56") (pin "2") (pinfunction "2_2") (pintype "passive"))
      (node (ref "C60") (pin "1") (pinfunction "1_1") (pintype "passive"))
    )
    (net (code "26") (name "Net-(C59-Pad2)") (class "Default")
      (node (ref "C59") (pin "2") (pinfunction "2_2") (pintype "passive"))
      (node (ref "C73") (pin "1") (pinfunction "1_1") (pintype "passive"))
    )
    (net (code "27") (name "Net-(D1-PadCATHODE)") (class "Default")
      (node (ref "D1") (pin "CATHODE") (pinfunction "CATHODE_CATHODE") (pintype "power_in"))
      (node (ref "R1") (pin "P$2") (pinfunction "P$2_P$2") (pintype "bidirectional"))
    )
    (net (code "28") (name "Net-(D3-PadCATHODE)") (class "Default")
      (node (ref "D3") (pin "CATHODE") (pinfunction "CATHODE_CATHODE") (pintype "power_in"))
      (node (ref "R14") (pin "P$2") (pinfunction "P$2_P$2") (pintype "bidirectional"))
    )
    (net (code "29") (name "Net-(D5-PadCATHODE)") (class "Default")
      (node (ref "D5") (pin "CATHODE") (pinfunction "CATHODE_CATHODE") (pintype "power_in"))
      (node (ref "R18") (pin "P$2") (pinfunction "P$2_P$2") (pintype "bidirectional"))
    )
    (net (code "30") (name "Net-(IC5-NR{slash}FB)") (class "Default")
      (node (ref "C13") (pin "1") (pinfunction "1_1") (pintype "passive"))
      (node (ref "IC5") (pin "4") (pinfunction "NR/FB_4") (pintype "bidirectional"))
    )
    (net (code "31") (name "Net-(PS1-BOOT)") (class "Default")
      (node (ref "C37") (pin "2") (pinfunction "2_2") (pintype "passive"))
      (node (ref "PS1") (pin "7") (pinfunction "BOOT_7") (pintype "bidirectional"))
    )
    (net (code "32") (name "Net-(PS1-FB)") (class "Default")
      (node (ref "PS1") (pin "5") (pinfunction "FB_5") (pintype "bidirectional"))
      (node (ref "R23") (pin "P$1") (pinfunction "P$1_P$1") (pintype "bidirectional"))
      (node (ref "R25") (pin "P$2") (pinfunction "P$2_P$2") (pintype "bidirectional"))
    )
    (net (code "33") (name "Net-(PS1-SW)") (class "Default")
      (node (ref "C37") (pin "1") (pinfunction "1_1") (pintype "passive"))
      (node (ref "L3") (pin "1") (pinfunction "1_1") (pintype "passive"))
      (node (ref "PS1") (pin "8") (pinfunction "SW_8") (pintype "bidirectional"))
    )
    (net (code "34") (name "Net-(PS1-VCC)") (class "Default")
      (node (ref "C44") (pin "1") (pinfunction "1_1") (pintype "passive"))
      (node (ref "PS1") (pin "6") (pinfunction "VCC_6") (pintype "bidirectional"))
    )
    (net (code "35") (name "Net-(PS3-BOOT)") (class "Default")
      (node (ref "C8") (pin "2") (pinfunction "2_2") (pintype "passive"))
      (node (ref "PS3") (pin "7") (pinfunction "BOOT_7") (pintype "bidirectional"))
    )
    (net (code "36") (name "Net-(PS3-FB)") (class "Default")
      (node (ref "PS3") (pin "5") (pinfunction "FB_5") (pintype "bidirectional"))
      (node (ref "R3") (pin "P$1") (pinfunction "P$1_P$1") (pintype "bidirectional"))
      (node (ref "R4") (pin "P$2") (pinfunction "P$2_P$2") (pintype "bidirectional"))
    )
    (net (code "37") (name "Net-(PS3-SW)") (class "Default")
      (node (ref "C8") (pin "1") (pinfunction "1_1") (pintype "passive"))
      (node (ref "L2") (pin "1") (pinfunction "1_1") (pintype "passive"))
      (node (ref "PS3") (pin "8") (pinfunction "SW_8") (pintype "bidirectional"))
    )
    (net (code "38") (name "Net-(PS3-VCC)") (class "Default")
      (node (ref "C9") (pin "1") (pinfunction "1_1") (pintype "passive"))
      (node (ref "PS3") (pin "6") (pinfunction "VCC_6") (pintype "bidirectional"))
    )
    (net (code "39") (name "Net-(PS4-BOOT)") (class "Default")
      (node (ref "C18") (pin "2") (pinfunction "2_2") (pintype "passive"))
      (node (ref "PS4") (pin "7") (pinfunction "BOOT_7") (pintype "bidirectional"))
    )
    (net (code "40") (name "Net-(PS4-FB)") (class "Default")
      (node (ref "PS4") (pin "5") (pinfunction "FB_5") (pintype "bidirectional"))
      (node (ref "R6") (pin "P$1") (pinfunction "P$1_P$1") (pintype "bidirectional"))
      (node (ref "R7") (pin "P$2") (pinfunction "P$2_P$2") (pintype "bidirectional"))
    )
    (net (code "41") (name "Net-(PS4-SW)") (class "Default")
      (node (ref "C18") (pin "1") (pinfunction "1_1") (pintype "passive"))
      (node (ref "L4") (pin "1") (pinfunction "1_1") (pintype "passive"))
      (node (ref "PS4") (pin "8") (pinfunction "SW_8") (pintype "bidirectional"))
    )
    (net (code "42") (name "Net-(PS4-VCC)") (class "Default")
      (node (ref "C23") (pin "1") (pinfunction "1_1") (pintype "passive"))
      (node (ref "PS4") (pin "6") (pinfunction "VCC_6") (pintype "bidirectional"))
    )
    (net (code "43") (name "Net-(PS5-BOOT)") (class "Default")
      (node (ref "C31") (pin "2") (pinfunction "2_2") (pintype "passive"))
      (node (ref "PS5") (pin "7") (pinfunction "BOOT_7") (pintype "bidirectional"))
    )
    (net (code "44") (name "Net-(PS5-FB)") (class "Default")
      (node (ref "PS5") (pin "5") (pinfunction "FB_5") (pintype "bidirectional"))
      (node (ref "R11") (pin "P$2") (pinfunction "P$2_P$2") (pintype "bidirectional"))
      (node (ref "R8") (pin "P$1") (pinfunction "P$1_P$1") (pintype "bidirectional"))
    )
    (net (code "45") (name "Net-(PS5-SW)") (class "Default")
      (node (ref "C31") (pin "1") (pinfunction "1_1") (pintype "passive"))
      (node (ref "L5") (pin "1") (pinfunction "1_1") (pintype "passive"))
      (node (ref "PS5") (pin "8") (pinfunction "SW_8") (pintype "bidirectional"))
    )
    (net (code "46") (name "Net-(PS5-VCC)") (class "Default")
      (node (ref "C32") (pin "1") (pinfunction "1_1") (pintype "passive"))
      (node (ref "PS5") (pin "6") (pinfunction "VCC_6") (pintype "bidirectional"))
    )
    (net (code "47") (name "Net-(PS6-BOOT)") (class "Default")
      (node (ref "C40") (pin "2") (pinfunction "2_2") (pintype "passive"))
      (node (ref "PS6") (pin "7") (pinfunction "BOOT_7") (pintype "bidirectional"))
    )
    (net (code "48") (name "Net-(PS6-FB)") (class "Default")
      (node (ref "PS6") (pin "5") (pinfunction "FB_5") (pintype "bidirectional"))
      (node (ref "R12") (pin "P$1") (pinfunction "P$1_P$1") (pintype "bidirectional"))
      (node (ref "R13") (pin "P$2") (pinfunction "P$2_P$2") (pintype "bidirectional"))
    )
    (net (code "49") (name "Net-(PS6-SW)") (class "Default")
      (node (ref "C40") (pin "1") (pinfunction "1_1") (pintype "passive"))
      (node (ref "L6") (pin "1") (pinfunction "1_1") (pintype "passive"))
      (node (ref "PS6") (pin "8") (pinfunction "SW_8") (pintype "bidirectional"))
    )
    (net (code "50") (name "Net-(PS6-VCC)") (class "Default")
      (node (ref "C41") (pin "1") (pinfunction "1_1") (pintype "passive"))
      (node (ref "PS6") (pin "6") (pinfunction "VCC_6") (pintype "bidirectional"))
    )
    (net (code "51") (name "Net-(PS7-BOOT)") (class "Default")
      (node (ref "C49") (pin "2") (pinfunction "2_2") (pintype "passive"))
      (node (ref "PS7") (pin "7") (pinfunction "BOOT_7") (pintype "bidirectional"))
    )
    (net (code "52") (name "Net-(PS7-FB)") (class "Default")
      (node (ref "PS7") (pin "5") (pinfunction "FB_5") (pintype "bidirectional"))
      (node (ref "R15") (pin "P$1") (pinfunction "P$1_P$1") (pintype "bidirectional"))
      (node (ref "R16") (pin "P$2") (pinfunction "P$2_P$2") (pintype "bidirectional"))
    )
    (net (code "53") (name "Net-(PS7-SW)") (class "Default")
      (node (ref "C49") (pin "1") (pinfunction "1_1") (pintype "passive"))
      (node (ref "L7") (pin "1") (pinfunction "1_1") (pintype "passive"))
      (node (ref "PS7") (pin "8") (pinfunction "SW_8") (pintype "bidirectional"))
    )
    (net (code "54") (name "Net-(PS7-VCC)") (class "Default")
      (node (ref "C50") (pin "1") (pinfunction "1_1") (pintype "passive"))
      (node (ref "PS7") (pin "6") (pinfunction "VCC_6") (pintype "bidirectional"))
    )
    (net (code "55") (name "Net-(PS8-BOOT)") (class "Default")
      (node (ref "C54") (pin "2") (pinfunction "2_2") (pintype "passive"))
      (node (ref "PS8") (pin "7") (pinfunction "BOOT_7") (pintype "bidirectional"))
    )
    (net (code "56") (name "Net-(PS8-FB)") (class "Default")
      (node (ref "PS8") (pin "5") (pinfunction "FB_5") (pintype "bidirectional"))
      (node (ref "R19") (pin "P$1") (pinfunction "P$1_P$1") (pintype "bidirectional"))
      (node (ref "R20") (pin "P$2") (pinfunction "P$2_P$2") (pintype "bidirectional"))
    )
    (net (code "57") (name "Net-(PS8-SW)") (class "Default")
      (node (ref "C54") (pin "1") (pinfunction "1_1") (pintype "passive"))
      (node (ref "L8") (pin "1") (pinfunction "1_1") (pintype "passive"))
      (node (ref "PS8") (pin "8") (pinfunction "SW_8") (pintype "bidirectional"))
    )
    (net (code "58") (name "Net-(PS8-VCC)") (class "Default")
      (node (ref "C55") (pin "1") (pinfunction "1_1") (pintype "passive"))
      (node (ref "PS8") (pin "6") (pinfunction "VCC_6") (pintype "bidirectional"))
    )
    (net (code "59") (name "Net-(R16-PadP$1)") (class "Default")
      (node (ref "R16") (pin "P$1") (pinfunction "P$1_P$1") (pintype "bidirectional"))
      (node (ref "R2") (pin "P$2") (pinfunction "P$2_P$2") (pintype "bidirectional"))
    )
    (net (code "60") (name "unconnected-(IC3-50MV-Pad4)") (class "Default")
      (node (ref "IC3") (pin "4") (pinfunction "50MV_4") (pintype "bidirectional"))
    )
    (net (code "61") (name "unconnected-(IC3-100MV-Pad5)") (class "Default")
      (node (ref "IC3") (pin "5") (pinfunction "100MV_5") (pintype "bidirectional"))
    )
    (net (code "62") (name "unconnected-(IC3-200MV-Pad6)") (class "Default")
      (node (ref "IC3") (pin "6") (pinfunction "200MV_6") (pintype "bidirectional"))
    )
    (net (code "63") (name "unconnected-(IC3-FB-Pad2)") (class "Default")
      (node (ref "IC3") (pin "2") (pinfunction "FB_2") (pintype "bidirectional"))
    )
    (net (code "64") (name "unconnected-(IC3-SS-Pad11)") (class "Default")
      (node (ref "IC3") (pin "11") (pinfunction "SS_11") (pintype "bidirectional"))
    )
    (net (code "65") (name "unconnected-(IC5-EN-Pad3)") (class "Default")
      (node (ref "IC5") (pin "3") (pinfunction "EN_3") (pintype "bidirectional"))
    )
    (net (code "66") (name "unconnected-(IC7-1.6V-Pad10)") (class "Default")
      (node (ref "IC7") (pin "10") (pinfunction "1.6V_10") (pintype "bidirectional"))
    )
    (net (code "67") (name "unconnected-(IC7-50MV-Pad4)") (class "Default")
      (node (ref "IC7") (pin "4") (pinfunction "50MV_4") (pintype "bidirectional"))
    )
    (net (code "68") (name "unconnected-(IC7-100MV-Pad5)") (class "Default")
      (node (ref "IC7") (pin "5") (pinfunction "100MV_5") (pintype "bidirectional"))
    )
    (net (code "69") (name "unconnected-(IC7-FB-Pad2)") (class "Default")
      (node (ref "IC7") (pin "2") (pinfunction "FB_2") (pintype "bidirectional"))
    )
    (net (code "70") (name "unconnected-(IC7-SS-Pad11)") (class "Default")
      (node (ref "IC7") (pin "11") (pinfunction "SS_11") (pintype "bidirectional"))
    )
    (net (code "71") (name "unconnected-(IC9-1.6V-Pad10)") (class "Default")
      (node (ref "IC9") (pin "10") (pinfunction "1.6V_10") (pintype "bidirectional"))
    )
    (net (code "72") (name "unconnected-(IC9-50MV-Pad4)") (class "Default")
      (node (ref "IC9") (pin "4") (pinfunction "50MV_4") (pintype "bidirectional"))
    )
    (net (code "73") (name "unconnected-(IC9-100MV-Pad5)") (class "Default")
      (node (ref "IC9") (pin "5") (pinfunction "100MV_5") (pintype "bidirectional"))
    )
    (net (code "74") (name "unconnected-(IC9-800MV-Pad9)") (class "Default")
      (node (ref "IC9") (pin "9") (pinfunction "800MV_9") (pintype "bidirectional"))
    )
    (net (code "75") (name "unconnected-(IC9-FB-Pad2)") (class "Default")
      (node (ref "IC9") (pin "2") (pinfunction "FB_2") (pintype "bidirectional"))
    )
    (net (code "76") (name "unconnected-(IC9-SS-Pad11)") (class "Default")
      (node (ref "IC9") (pin "11") (pinfunction "SS_11") (pintype "bidirectional"))
    )
    (net (code "77") (name "unconnected-(IC11-1.6V-Pad10)") (class "Default")
      (node (ref "IC11") (pin "10") (pinfunction "1.6V_10") (pintype "bidirectional"))
    )
    (net (code "78") (name "unconnected-(IC11-50MV-Pad4)") (class "Default")
      (node (ref "IC11") (pin "4") (pinfunction "50MV_4") (pintype "bidirectional"))
    )
    (net (code "79") (name "unconnected-(IC11-100MV-Pad5)") (class "Default")
      (node (ref "IC11") (pin "5") (pinfunction "100MV_5") (pintype "bidirectional"))
    )
    (net (code "80") (name "unconnected-(IC11-FB-Pad2)") (class "Default")
      (node (ref "IC11") (pin "2") (pinfunction "FB_2") (pintype "bidirectional"))
    )
    (net (code "81") (name "unconnected-(IC11-SS-Pad11)") (class "Default")
      (node (ref "IC11") (pin "11") (pinfunction "SS_11") (pintype "bidirectional"))
    )
    (net (code "82") (name "unconnected-(IC12-50MV-Pad4)") (class "Default")
      (node (ref "IC12") (pin "4") (pinfunction "50MV_4") (pintype "bidirectional"))
    )
    (net (code "83") (name "unconnected-(IC12-100MV-Pad5)") (class "Default")
      (node (ref "IC12") (pin "5") (pinfunction "100MV_5") (pintype "bidirectional"))
    )
    (net (code "84") (name "unconnected-(IC12-200MV-Pad6)") (class "Default")
      (node (ref "IC12") (pin "6") (pinfunction "200MV_6") (pintype "bidirectional"))
    )
    (net (code "85") (name "unconnected-(IC12-800MV-Pad9)") (class "Default")
      (node (ref "IC12") (pin "9") (pinfunction "800MV_9") (pintype "bidirectional"))
    )
    (net (code "86") (name "unconnected-(IC12-FB-Pad2)") (class "Default")
      (node (ref "IC12") (pin "2") (pinfunction "FB_2") (pintype "bidirectional"))
    )
    (net (code "87") (name "unconnected-(IC12-SS-Pad11)") (class "Default")
      (node (ref "IC12") (pin "11") (pinfunction "SS_11") (pintype "bidirectional"))
    )
    (net (code "88") (name "unconnected-(IC14-50MV-Pad4)") (class "Default")
      (node (ref "IC14") (pin "4") (pinfunction "50MV_4") (pintype "bidirectional"))
    )
    (net (code "89") (name "unconnected-(IC14-100MV-Pad5)") (class "Default")
      (node (ref "IC14") (pin "5") (pinfunction "100MV_5") (pintype "bidirectional"))
    )
    (net (code "90") (name "unconnected-(IC14-200MV-Pad6)") (class "Default")
      (node (ref "IC14") (pin "6") (pinfunction "200MV_6") (pintype "bidirectional"))
    )
    (net (code "91") (name "unconnected-(IC14-800MV-Pad9)") (class "Default")
      (node (ref "IC14") (pin "9") (pinfunction "800MV_9") (pintype "bidirectional"))
    )
    (net (code "92") (name "unconnected-(IC14-FB-Pad2)") (class "Default")
      (node (ref "IC14") (pin "2") (pinfunction "FB_2") (pintype "bidirectional"))
    )
    (net (code "93") (name "unconnected-(IC14-SS-Pad11)") (class "Default")
      (node (ref "IC14") (pin "11") (pinfunction "SS_11") (pintype "bidirectional"))
    )
    (net (code "94") (name "unconnected-(PS1-PG-Pad4)") (class "Default")
      (node (ref "PS1") (pin "4") (pinfunction "PG_4") (pintype "bidirectional"))
    )
    (net (code "95") (name "unconnected-(PS3-PG-Pad4)") (class "Default")
      (node (ref "PS3") (pin "4") (pinfunction "PG_4") (pintype "bidirectional"))
    )
    (net (code "96") (name "unconnected-(PS4-PG-Pad4)") (class "Default")
      (node (ref "PS4") (pin "4") (pinfunction "PG_4") (pintype "bidirectional"))
    )
    (net (code "97") (name "unconnected-(PS5-PG-Pad4)") (class "Default")
      (node (ref "PS5") (pin "4") (pinfunction "PG_4") (pintype "bidirectional"))
    )
    (net (code "98") (name "unconnected-(PS6-PG-Pad4)") (class "Default")
      (node (ref "PS6") (pin "4") (pinfunction "PG_4") (pintype "bidirectional"))
    )
    (net (code "99") (name "unconnected-(PS7-PG-Pad4)") (class "Default")
      (node (ref "PS7") (pin "4") (pinfunction "PG_4") (pintype "bidirectional"))
    )
    (net (code "100") (name "unconnected-(PS8-PG-Pad4)") (class "Default")
      (node (ref "PS8") (pin "4") (pinfunction "PG_4") (pintype "bidirectional"))
    )
  )
)
